# DMXW_Driver_Board.net
KiCad netlist of a schematic drawn in EAGLE
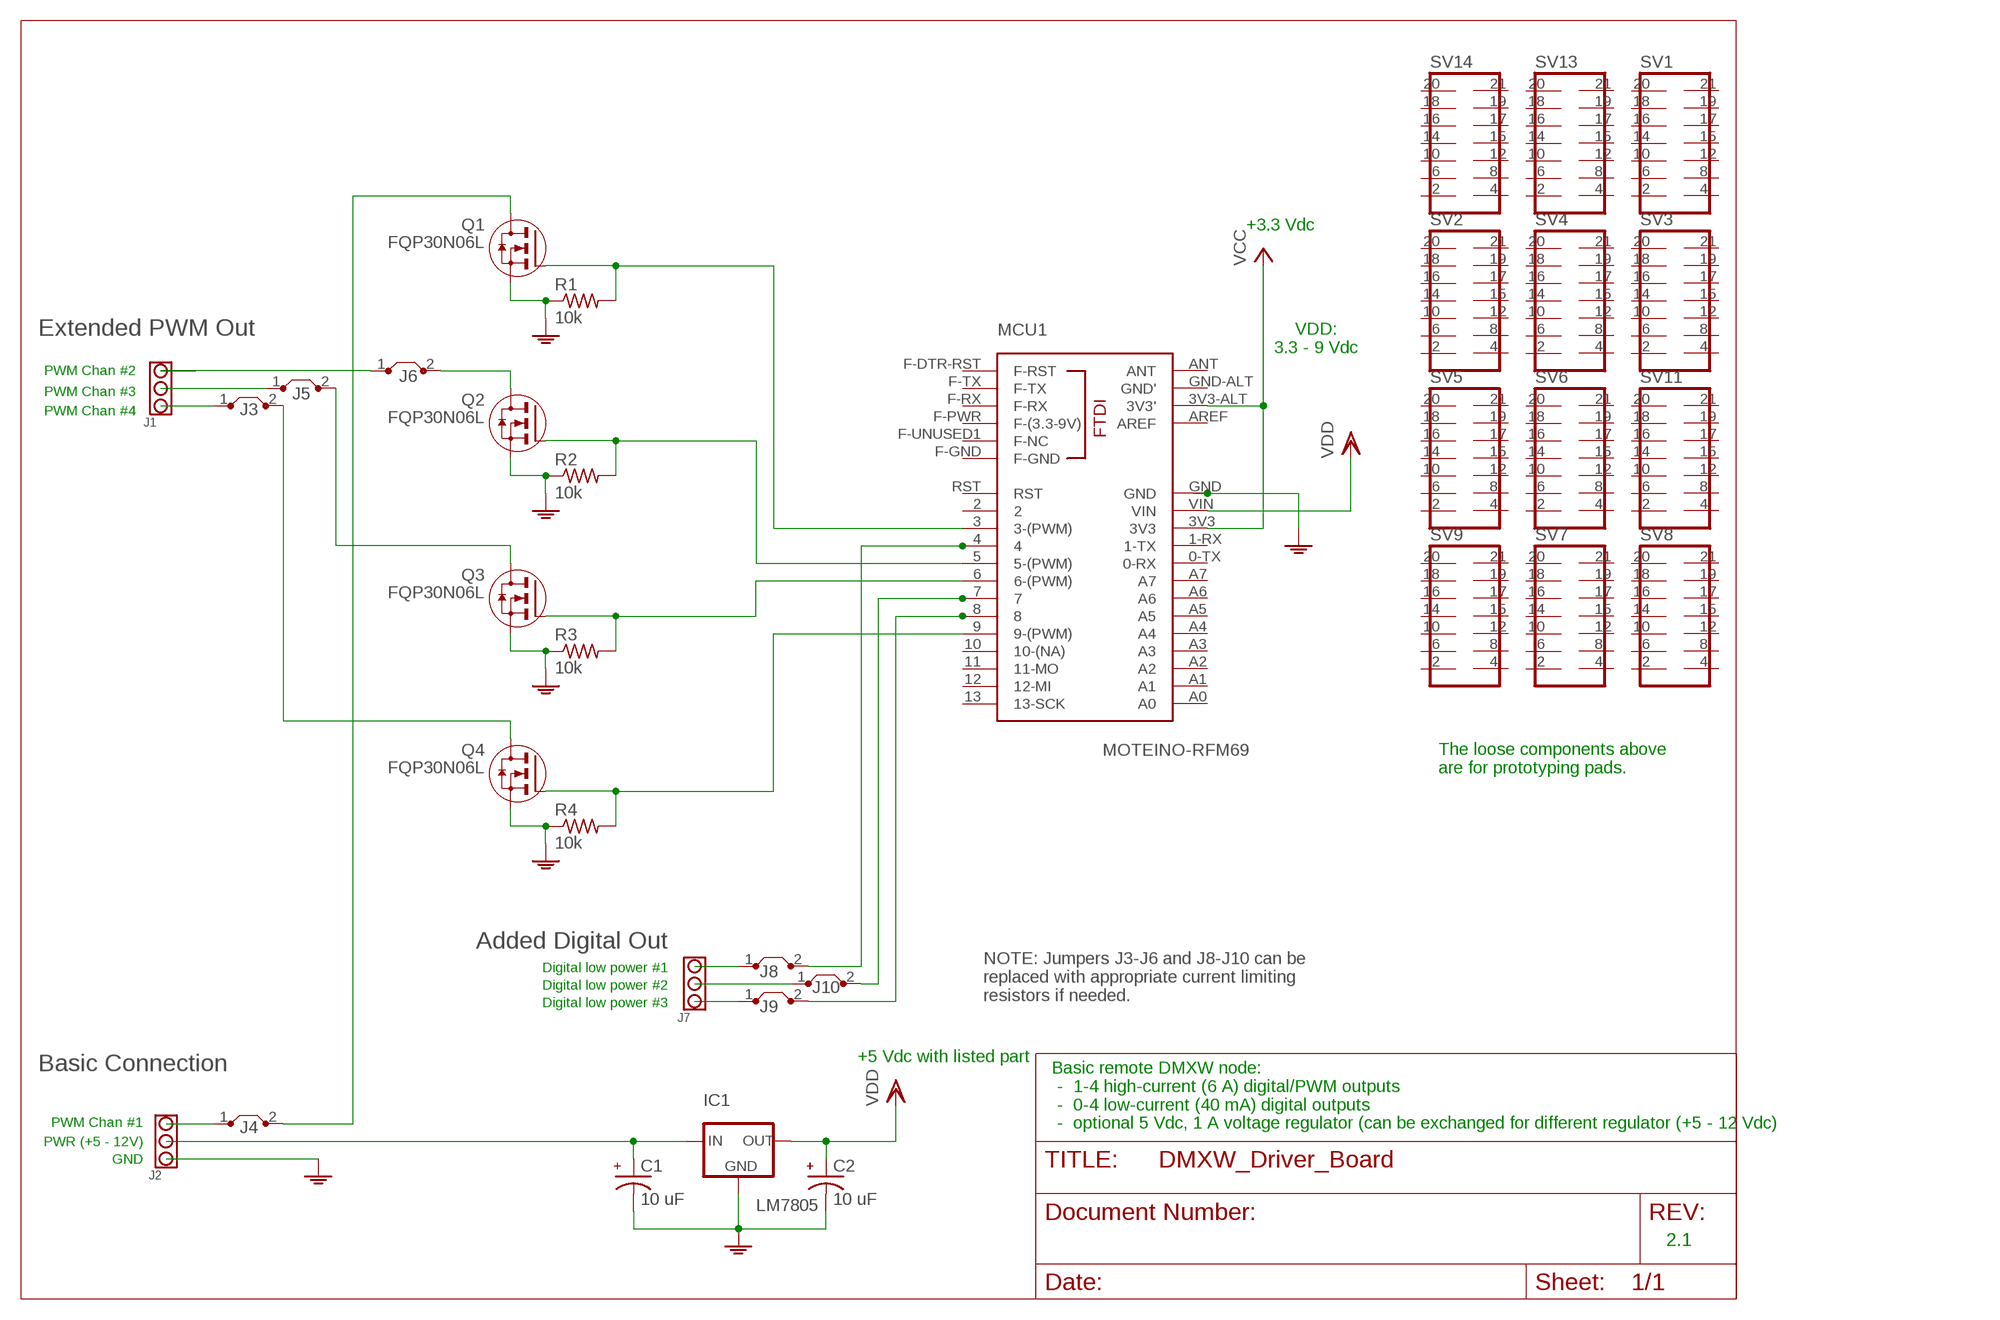
[diagram p0: schematic, sheet 1]

(export (version "E")
  (design (tool "Eeschema 10.0.6"))
  (components
    (comp (ref "C1")
      (value "10 uF")
      (footprint "eagle-import:RADIAL-CANISTER")
      (libsource (lib "eagle-import") (part "CAPACITOR-ELECTROLYTICRADIALCANISTER"))
    )
    (comp (ref "C2")
      (value "10 uF")
      (footprint "eagle-import:RADIAL-CANISTER")
      (libsource (lib "eagle-import") (part "CAPACITOR-ELECTROLYTICRADIALCANISTER"))
    )
    (comp (ref "IC1")
      (value "LM7805")
      (footprint "eagle-import:TO-220-HORIZONTAL")
      (libsource (lib "eagle-import") (part "78XX-VOLTAGEREGULATORSHOZ"))
    )
    (comp (ref "J1")
      (value "TERMINAL-BLOCK-3")
      (footprint "eagle-import:W237-103")
      (libsource (lib "eagle-import") (part "TERMINAL-BLOCK-3"))
    )
    (comp (ref "J2")
      (value "TERMINAL-BLOCK-3")
      (footprint "eagle-import:W237-103")
      (libsource (lib "eagle-import") (part "TERMINAL-BLOCK-3"))
    )
    (comp (ref "J3")
      (value "J5MM")
      (footprint "eagle-import:05")
      (libsource (lib "eagle-import") (part "J5MM"))
    )
    (comp (ref "J4")
      (value "J5MM")
      (footprint "eagle-import:05")
      (libsource (lib "eagle-import") (part "J5MM"))
    )
    (comp (ref "J5")
      (value "J5MM")
      (footprint "eagle-import:05")
      (libsource (lib "eagle-import") (part "J5MM"))
    )
    (comp (ref "J6")
      (value "J5MM")
      (footprint "eagle-import:05")
      (libsource (lib "eagle-import") (part "J5MM"))
    )
    (comp (ref "J7")
      (value "TERMINAL-BLOCK-3")
      (footprint "eagle-import:W237-103")
      (libsource (lib "eagle-import") (part "TERMINAL-BLOCK-3"))
    )
    (comp (ref "J8")
      (value "J5MM")
      (footprint "eagle-import:05")
      (libsource (lib "eagle-import") (part "J5MM"))
    )
    (comp (ref "J9")
      (value "J5MM")
      (footprint "eagle-import:05")
      (libsource (lib "eagle-import") (part "J5MM"))
    )
    (comp (ref "J10")
      (value "J5MM")
      (footprint "eagle-import:05")
      (libsource (lib "eagle-import") (part "J5MM"))
    )
    (comp (ref "MCU1")
      (value "MOTEINO-RFM69")
      (footprint "eagle-import:MOTEINO")
      (libsource (lib "eagle-import") (part "MOTEINO-RFM69"))
    )
    (comp (ref "Q1")
      (value "FQP30N06L")
      (footprint "eagle-import:TO-220-HORIZONTAL")
      (libsource (lib "eagle-import") (part "MOSFET-N-FQP30N06LHORIZ"))
    )
    (comp (ref "Q2")
      (value "FQP30N06L")
      (footprint "eagle-import:TO-220-HORIZONTAL")
      (libsource (lib "eagle-import") (part "MOSFET-N-FQP30N06LHORIZ"))
    )
    (comp (ref "Q3")
      (value "FQP30N06L")
      (footprint "eagle-import:TO-220-HORIZONTAL")
      (libsource (lib "eagle-import") (part "MOSFET-N-FQP30N06LHORIZ"))
    )
    (comp (ref "Q4")
      (value "FQP30N06L")
      (footprint "eagle-import:TO-220-HORIZONTAL")
      (libsource (lib "eagle-import") (part "MOSFET-N-FQP30N06LHORIZ"))
    )
    (comp (ref "R1")
      (value "10k")
      (footprint "eagle-import:0207_10")
      (libsource (lib "eagle-import") (part "R-US_0207/10"))
    )
    (comp (ref "R2")
      (value "10k")
      (footprint "eagle-import:0207_10")
      (libsource (lib "eagle-import") (part "R-US_0207/10"))
    )
    (comp (ref "R3")
      (value "10k")
      (footprint "eagle-import:0207_10")
      (libsource (lib "eagle-import") (part "R-US_0207/10"))
    )
    (comp (ref "R4")
      (value "10k")
      (footprint "eagle-import:0207_10")
      (libsource (lib "eagle-import") (part "R-US_0207/10"))
    )
    (comp (ref "SV1")
      (value "14P")
      (footprint "eagle-import:14P")
      (libsource (lib "eagle-import") (part "14P"))
    )
    (comp (ref "SV2")
      (value "14P")
      (footprint "eagle-import:14P")
      (libsource (lib "eagle-import") (part "14P"))
    )
    (comp (ref "SV3")
      (value "14P")
      (footprint "eagle-import:14P")
      (libsource (lib "eagle-import") (part "14P"))
    )
    (comp (ref "SV4")
      (value "14P")
      (footprint "eagle-import:14P")
      (libsource (lib "eagle-import") (part "14P"))
    )
    (comp (ref "SV5")
      (value "14P")
      (footprint "eagle-import:14P")
      (libsource (lib "eagle-import") (part "14P"))
    )
    (comp (ref "SV6")
      (value "14P")
      (footprint "eagle-import:14P")
      (libsource (lib "eagle-import") (part "14P"))
    )
    (comp (ref "SV7")
      (value "14P")
      (footprint "eagle-import:14P")
      (libsource (lib "eagle-import") (part "14P"))
    )
    (comp (ref "SV8")
      (value "14P")
      (footprint "eagle-import:14P")
      (libsource (lib "eagle-import") (part "14P"))
    )
    (comp (ref "SV9")
      (value "14P")
      (footprint "eagle-import:14P")
      (libsource (lib "eagle-import") (part "14P"))
    )
    (comp (ref "SV11")
      (value "14P")
      (footprint "eagle-import:14P")
      (libsource (lib "eagle-import") (part "14P"))
    )
    (comp (ref "SV13")
      (value "14P")
      (footprint "eagle-import:14P")
      (libsource (lib "eagle-import") (part "14P"))
    )
    (comp (ref "SV14")
      (value "14P")
      (footprint "eagle-import:14P")
      (libsource (lib "eagle-import") (part "14P"))
    )
  )
  (nets
    (net (code "1") (name "GND") (class "Default")
      (node (ref "C1") (pin "-") (pinfunction "-_-") (pintype "passive"))
      (node (ref "C2") (pin "-") (pinfunction "-_-") (pintype "passive"))
      (node (ref "IC1") (pin "PIN2") (pinfunction "GND_PIN2") (pintype "input"))
      (node (ref "J2") (pin "3") (pinfunction "P$3_3") (pintype "bidirectional"))
      (node (ref "MCU1") (pin "GND") (pinfunction "GND_GND") (pintype "bidirectional"))
      (node (ref "Q1") (pin "PIN3") (pinfunction "S_PIN3") (pintype "passive"))
      (node (ref "Q2") (pin "PIN3") (pinfunction "S_PIN3") (pintype "passive"))
      (node (ref "Q3") (pin "PIN3") (pinfunction "S_PIN3") (pintype "passive"))
      (node (ref "Q4") (pin "PIN3") (pinfunction "S_PIN3") (pintype "passive"))
      (node (ref "R1") (pin "1") (pinfunction "1_1") (pintype "passive"))
      (node (ref "R2") (pin "1") (pinfunction "1_1") (pintype "passive"))
      (node (ref "R3") (pin "1") (pinfunction "1_1") (pintype "passive"))
      (node (ref "R4") (pin "1") (pinfunction "1_1") (pintype "passive"))
    )
    (net (code "2") (name "Net-(IC1-IN)") (class "Default")
      (node (ref "C1") (pin "+") (pinfunction "+_+") (pintype "passive"))
      (node (ref "IC1") (pin "PIN1") (pinfunction "IN_PIN1") (pintype "input"))
      (node (ref "J2") (pin "2") (pinfunction "P$2_2") (pintype "bidirectional"))
    )
    (net (code "3") (name "Net-(J1-P$1)") (class "Default")
      (node (ref "J1") (pin "1") (pinfunction "P$1_1") (pintype "bidirectional"))
      (node (ref "J6") (pin "1") (pinfunction "1_1") (pintype "passive"))
    )
    (net (code "4") (name "Net-(J1-P$2)") (class "Default")
      (node (ref "J1") (pin "2") (pinfunction "P$2_2") (pintype "bidirectional"))
      (node (ref "J5") (pin "1") (pinfunction "1_1") (pintype "passive"))
    )
    (net (code "5") (name "Net-(J1-P$3)") (class "Default")
      (node (ref "J1") (pin "3") (pinfunction "P$3_3") (pintype "bidirectional"))
      (node (ref "J3") (pin "1") (pinfunction "1_1") (pintype "passive"))
    )
    (net (code "6") (name "Net-(J2-P$1)") (class "Default")
      (node (ref "J2") (pin "1") (pinfunction "P$1_1") (pintype "bidirectional"))
      (node (ref "J4") (pin "1") (pinfunction "1_1") (pintype "passive"))
    )
    (net (code "7") (name "Net-(J7-P$1)") (class "Default")
      (node (ref "J7") (pin "1") (pinfunction "P$1_1") (pintype "bidirectional"))
      (node (ref "J8") (pin "1") (pinfunction "1_1") (pintype "passive"))
    )
    (net (code "8") (name "Net-(J7-P$2)") (class "Default")
      (node (ref "J10") (pin "1") (pinfunction "1_1") (pintype "passive"))
      (node (ref "J7") (pin "2") (pinfunction "P$2_2") (pintype "bidirectional"))
    )
    (net (code "9") (name "Net-(J7-P$3)") (class "Default")
      (node (ref "J7") (pin "3") (pinfunction "P$3_3") (pintype "bidirectional"))
      (node (ref "J9") (pin "1") (pinfunction "1_1") (pintype "passive"))
    )
    (net (code "10") (name "Net-(J8-Pad2)") (class "Default")
      (node (ref "J8") (pin "2") (pinfunction "2_2") (pintype "passive"))
      (node (ref "MCU1") (pin "4") (pinfunction "4_4") (pintype "bidirectional"))
    )
    (net (code "11") (name "Net-(J9-Pad2)") (class "Default")
      (node (ref "J9") (pin "2") (pinfunction "2_2") (pintype "passive"))
      (node (ref "MCU1") (pin "8") (pinfunction "8_8") (pintype "bidirectional"))
    )
    (net (code "12") (name "Net-(J10-Pad2)") (class "Default")
      (node (ref "J10") (pin "2") (pinfunction "2_2") (pintype "passive"))
      (node (ref "MCU1") (pin "7") (pinfunction "7_7") (pintype "bidirectional"))
    )
    (net (code "13") (name "Net-(MCU1-3-(PWM))") (class "Default")
      (node (ref "MCU1") (pin "3") (pinfunction "3-(PWM)_3") (pintype "bidirectional"))
      (node (ref "Q1") (pin "PIN1") (pinfunction "G_PIN1") (pintype "passive"))
      (node (ref "R1") (pin "2") (pinfunction "2_2") (pintype "passive"))
    )
    (net (code "14") (name "Net-(MCU1-5-(PWM))") (class "Default")
      (node (ref "MCU1") (pin "5") (pinfunction "5-(PWM)_5") (pintype "bidirectional"))
      (node (ref "Q2") (pin "PIN1") (pinfunction "G_PIN1") (pintype "passive"))
      (node (ref "R2") (pin "2") (pinfunction "2_2") (pintype "passive"))
    )
    (net (code "15") (name "Net-(MCU1-6-(PWM))") (class "Default")
      (node (ref "MCU1") (pin "6") (pinfunction "6-(PWM)_6") (pintype "bidirectional"))
      (node (ref "Q3") (pin "PIN1") (pinfunction "G_PIN1") (pintype "passive"))
      (node (ref "R3") (pin "2") (pinfunction "2_2") (pintype "passive"))
    )
    (net (code "16") (name "Net-(MCU1-9-(PWM))") (class "Default")
      (node (ref "MCU1") (pin "9") (pinfunction "9-(PWM)_9") (pintype "bidirectional"))
      (node (ref "Q4") (pin "PIN1") (pinfunction "G_PIN1") (pintype "passive"))
      (node (ref "R4") (pin "2") (pinfunction "2_2") (pintype "passive"))
    )
    (net (code "17") (name "Net-(Q1-D)") (class "Default")
      (node (ref "J4") (pin "2") (pinfunction "2_2") (pintype "passive"))
      (node (ref "Q1") (pin "PIN2") (pinfunction "D_PIN2") (pintype "passive"))
    )
    (net (code "18") (name "Net-(Q2-D)") (class "Default")
      (node (ref "J6") (pin "2") (pinfunction "2_2") (pintype "passive"))
      (node (ref "Q2") (pin "PIN2") (pinfunction "D_PIN2") (pintype "passive"))
    )
    (net (code "19") (name "Net-(Q3-D)") (class "Default")
      (node (ref "J5") (pin "2") (pinfunction "2_2") (pintype "passive"))
      (node (ref "Q3") (pin "PIN2") (pinfunction "D_PIN2") (pintype "passive"))
    )
    (net (code "20") (name "Net-(Q4-D)") (class "Default")
      (node (ref "J3") (pin "2") (pinfunction "2_2") (pintype "passive"))
      (node (ref "Q4") (pin "PIN2") (pinfunction "D_PIN2") (pintype "passive"))
    )
    (net (code "21") (name "VCC") (class "Default")
      (node (ref "MCU1") (pin "3V3") (pinfunction "3V3_3V3") (pintype "bidirectional"))
      (node (ref "MCU1") (pin "3V3-ALT") (pinfunction "3V3'_3V3-ALT") (pintype "bidirectional"))
    )
    (net (code "22") (name "VDD") (class "Default")
      (node (ref "C2") (pin "+") (pinfunction "+_+") (pintype "passive"))
      (node (ref "IC1") (pin "PIN3") (pinfunction "OUT_PIN3") (pintype "passive"))
      (node (ref "MCU1") (pin "VIN") (pinfunction "VIN_VIN") (pintype "bidirectional"))
    )
    (net (code "23") (name "unconnected-(MCU1-0-RX-Pad0-TX)") (class "Default")
      (node (ref "MCU1") (pin "0-TX") (pinfunction "0-RX_0-TX") (pintype "bidirectional"))
    )
    (net (code "24") (name "unconnected-(MCU1-1-TX-Pad1-RX)") (class "Default")
      (node (ref "MCU1") (pin "1-RX") (pinfunction "1-TX_1-RX") (pintype "bidirectional"))
    )
    (net (code "25") (name "unconnected-(MCU1-10-(NA)-Pad10)") (class "Default")
      (node (ref "MCU1") (pin "10") (pinfunction "10-(NA)_10") (pintype "bidirectional"))
    )
    (net (code "26") (name "unconnected-(MCU1-11-MO-Pad11)") (class "Default")
      (node (ref "MCU1") (pin "11") (pinfunction "11-MO_11") (pintype "bidirectional"))
    )
    (net (code "27") (name "unconnected-(MCU1-12-MI-Pad12)") (class "Default")
      (node (ref "MCU1") (pin "12") (pinfunction "12-MI_12") (pintype "bidirectional"))
    )
    (net (code "28") (name "unconnected-(MCU1-13-SCK-Pad13)") (class "Default")
      (node (ref "MCU1") (pin "13") (pinfunction "13-SCK_13") (pintype "bidirectional"))
    )
    (net (code "29") (name "unconnected-(MCU1-F-(3.3-9V)-PadF-PWR)") (class "Default")
      (node (ref "MCU1") (pin "F-PWR") (pinfunction "F-(3.3-9V)_F-PWR") (pintype "bidirectional"))
    )
    (net (code "30") (name "unconnected-(MCU1-F-NC-PadF-UNUSED1)") (class "Default")
      (node (ref "MCU1") (pin "F-UNUSED1") (pinfunction "F-NC_F-UNUSED1") (pintype "bidirectional"))
    )
    (net (code "31") (name "unconnected-(MCU1-F-RST-PadF-DTR-RST)") (class "Default")
      (node (ref "MCU1") (pin "F-DTR-RST") (pinfunction "F-RST_F-DTR-RST") (pintype "bidirectional"))
    )
    (net (code "32") (name "unconnected-(MCU1-GND'-PadGND-ALT)") (class "Default")
      (node (ref "MCU1") (pin "GND-ALT") (pinfunction "GND'_GND-ALT") (pintype "bidirectional"))
    )
    (net (code "33") (name "unconnected-(MCU1-Pad2)") (class "Default")
      (node (ref "MCU1") (pin "2") (pinfunction "2_2") (pintype "bidirectional"))
    )
    (net (code "34") (name "unconnected-(MCU1-PadA0)") (class "Default")
      (node (ref "MCU1") (pin "A0") (pinfunction "A0_A0") (pintype "bidirectional"))
    )
    (net (code "35") (name "unconnected-(MCU1-PadA1)") (class "Default")
      (node (ref "MCU1") (pin "A1") (pinfunction "A1_A1") (pintype "bidirectional"))
    )
    (net (code "36") (name "unconnected-(MCU1-PadA2)") (class "Default")
      (node (ref "MCU1") (pin "A2") (pinfunction "A2_A2") (pintype "bidirectional"))
    )
    (net (code "37") (name "unconnected-(MCU1-PadA3)") (class "Default")
      (node (ref "MCU1") (pin "A3") (pinfunction "A3_A3") (pintype "bidirectional"))
    )
    (net (code "38") (name "unconnected-(MCU1-PadA4)") (class "Default")
      (node (ref "MCU1") (pin "A4") (pinfunction "A4_A4") (pintype "bidirectional"))
    )
    (net (code "39") (name "unconnected-(MCU1-PadA5)") (class "Default")
      (node (ref "MCU1") (pin "A5") (pinfunction "A5_A5") (pintype "bidirectional"))
    )
    (net (code "40") (name "unconnected-(MCU1-PadA6)") (class "Default")
      (node (ref "MCU1") (pin "A6") (pinfunction "A6_A6") (pintype "bidirectional"))
    )
    (net (code "41") (name "unconnected-(MCU1-PadA7)") (class "Default")
      (node (ref "MCU1") (pin "A7") (pinfunction "A7_A7") (pintype "bidirectional"))
    )
    (net (code "42") (name "unconnected-(MCU1-PadANT)") (class "Default")
      (node (ref "MCU1") (pin "ANT") (pinfunction "ANT_ANT") (pintype "bidirectional"))
    )
    (net (code "43") (name "unconnected-(MCU1-PadAREF)") (class "Default")
      (node (ref "MCU1") (pin "AREF") (pinfunction "AREF_AREF") (pintype "bidirectional"))
    )
    (net (code "44") (name "unconnected-(MCU1-PadF-GND)") (class "Default")
      (node (ref "MCU1") (pin "F-GND") (pinfunction "F-GND_F-GND") (pintype "bidirectional"))
    )
    (net (code "45") (name "unconnected-(MCU1-PadF-RX)") (class "Default")
      (node (ref "MCU1") (pin "F-RX") (pinfunction "F-RX_F-RX") (pintype "bidirectional"))
    )
    (net (code "46") (name "unconnected-(MCU1-PadF-TX)") (class "Default")
      (node (ref "MCU1") (pin "F-TX") (pinfunction "F-TX_F-TX") (pintype "bidirectional"))
    )
    (net (code "47") (name "unconnected-(MCU1-PadRST)") (class "Default")
      (node (ref "MCU1") (pin "RST") (pinfunction "RST_RST") (pintype "bidirectional"))
    )
    (net (code "48") (name "unconnected-(SV1-1-Pad2)") (class "Default")
      (node (ref "SV1") (pin "2") (pinfunction "1_2") (pintype "passive"))
    )
    (net (code "49") (name "unconnected-(SV1-2-Pad4)") (class "Default")
      (node (ref "SV1") (pin "4") (pinfunction "2_4") (pintype "passive"))
    )
    (net (code "50") (name "unconnected-(SV1-3-Pad6)") (class "Default")
      (node (ref "SV1") (pin "6") (pinfunction "3_6") (pintype "passive"))
    )
    (net (code "51") (name "unconnected-(SV1-4-Pad8)") (class "Default")
      (node (ref "SV1") (pin "8") (pinfunction "4_8") (pintype "passive"))
    )
    (net (code "52") (name "unconnected-(SV1-5-Pad10)") (class "Default")
      (node (ref "SV1") (pin "10") (pinfunction "5_10") (pintype "passive"))
    )
    (net (code "53") (name "unconnected-(SV1-6-Pad12)") (class "Default")
      (node (ref "SV1") (pin "12") (pinfunction "6_12") (pintype "passive"))
    )
    (net (code "54") (name "unconnected-(SV1-7-Pad14)") (class "Default")
      (node (ref "SV1") (pin "14") (pinfunction "7_14") (pintype "passive"))
    )
    (net (code "55") (name "unconnected-(SV1-8-Pad15)") (class "Default")
      (node (ref "SV1") (pin "15") (pinfunction "8_15") (pintype "passive"))
    )
    (net (code "56") (name "unconnected-(SV1-9-Pad16)") (class "Default")
      (node (ref "SV1") (pin "16") (pinfunction "9_16") (pintype "passive"))
    )
    (net (code "57") (name "unconnected-(SV1-10-Pad17)") (class "Default")
      (node (ref "SV1") (pin "17") (pinfunction "10_17") (pintype "passive"))
    )
    (net (code "58") (name "unconnected-(SV1-11-Pad18)") (class "Default")
      (node (ref "SV1") (pin "18") (pinfunction "11_18") (pintype "passive"))
    )
    (net (code "59") (name "unconnected-(SV1-12-Pad19)") (class "Default")
      (node (ref "SV1") (pin "19") (pinfunction "12_19") (pintype "passive"))
    )
    (net (code "60") (name "unconnected-(SV1-13-Pad20)") (class "Default")
      (node (ref "SV1") (pin "20") (pinfunction "13_20") (pintype "passive"))
    )
    (net (code "61") (name "unconnected-(SV1-14-Pad21)") (class "Default")
      (node (ref "SV1") (pin "21") (pinfunction "14_21") (pintype "passive"))
    )
    (net (code "62") (name "unconnected-(SV2-1-Pad2)") (class "Default")
      (node (ref "SV2") (pin "2") (pinfunction "1_2") (pintype "passive"))
    )
    (net (code "63") (name "unconnected-(SV2-2-Pad4)") (class "Default")
      (node (ref "SV2") (pin "4") (pinfunction "2_4") (pintype "passive"))
    )
    (net (code "64") (name "unconnected-(SV2-3-Pad6)") (class "Default")
      (node (ref "SV2") (pin "6") (pinfunction "3_6") (pintype "passive"))
    )
    (net (code "65") (name "unconnected-(SV2-4-Pad8)") (class "Default")
      (node (ref "SV2") (pin "8") (pinfunction "4_8") (pintype "passive"))
    )
    (net (code "66") (name "unconnected-(SV2-5-Pad10)") (class "Default")
      (node (ref "SV2") (pin "10") (pinfunction "5_10") (pintype "passive"))
    )
    (net (code "67") (name "unconnected-(SV2-6-Pad12)") (class "Default")
      (node (ref "SV2") (pin "12") (pinfunction "6_12") (pintype "passive"))
    )
    (net (code "68") (name "unconnected-(SV2-7-Pad14)") (class "Default")
      (node (ref "SV2") (pin "14") (pinfunction "7_14") (pintype "passive"))
    )
    (net (code "69") (name "unconnected-(SV2-8-Pad15)") (class "Default")
      (node (ref "SV2") (pin "15") (pinfunction "8_15") (pintype "passive"))
    )
    (net (code "70") (name "unconnected-(SV2-9-Pad16)") (class "Default")
      (node (ref "SV2") (pin "16") (pinfunction "9_16") (pintype "passive"))
    )
    (net (code "71") (name "unconnected-(SV2-10-Pad17)") (class "Default")
      (node (ref "SV2") (pin "17") (pinfunction "10_17") (pintype "passive"))
    )
    (net (code "72") (name "unconnected-(SV2-11-Pad18)") (class "Default")
      (node (ref "SV2") (pin "18") (pinfunction "11_18") (pintype "passive"))
    )
    (net (code "73") (name "unconnected-(SV2-12-Pad19)") (class "Default")
      (node (ref "SV2") (pin "19") (pinfunction "12_19") (pintype "passive"))
    )
    (net (code "74") (name "unconnected-(SV2-13-Pad20)") (class "Default")
      (node (ref "SV2") (pin "20") (pinfunction "13_20") (pintype "passive"))
    )
    (net (code "75") (name "unconnected-(SV2-14-Pad21)") (class "Default")
      (node (ref "SV2") (pin "21") (pinfunction "14_21") (pintype "passive"))
    )
    (net (code "76") (name "unconnected-(SV3-1-Pad2)") (class "Default")
      (node (ref "SV3") (pin "2") (pinfunction "1_2") (pintype "passive"))
    )
    (net (code "77") (name "unconnected-(SV3-2-Pad4)") (class "Default")
      (node (ref "SV3") (pin "4") (pinfunction "2_4") (pintype "passive"))
    )
    (net (code "78") (name "unconnected-(SV3-3-Pad6)") (class "Default")
      (node (ref "SV3") (pin "6") (pinfunction "3_6") (pintype "passive"))
    )
    (net (code "79") (name "unconnected-(SV3-4-Pad8)") (class "Default")
      (node (ref "SV3") (pin "8") (pinfunction "4_8") (pintype "passive"))
    )
    (net (code "80") (name "unconnected-(SV3-5-Pad10)") (class "Default")
      (node (ref "SV3") (pin "10") (pinfunction "5_10") (pintype "passive"))
    )
    (net (code "81") (name "unconnected-(SV3-6-Pad12)") (class "Default")
      (node (ref "SV3") (pin "12") (pinfunction "6_12") (pintype "passive"))
    )
    (net (code "82") (name "unconnected-(SV3-7-Pad14)") (class "Default")
      (node (ref "SV3") (pin "14") (pinfunction "7_14") (pintype "passive"))
    )
    (net (code "83") (name "unconnected-(SV3-8-Pad15)") (class "Default")
      (node (ref "SV3") (pin "15") (pinfunction "8_15") (pintype "passive"))
    )
    (net (code "84") (name "unconnected-(SV3-9-Pad16)") (class "Default")
      (node (ref "SV3") (pin "16") (pinfunction "9_16") (pintype "passive"))
    )
    (net (code "85") (name "unconnected-(SV3-10-Pad17)") (class "Default")
      (node (ref "SV3") (pin "17") (pinfunction "10_17") (pintype "passive"))
    )
    (net (code "86") (name "unconnected-(SV3-11-Pad18)") (class "Default")
      (node (ref "SV3") (pin "18") (pinfunction "11_18") (pintype "passive"))
    )
    (net (code "87") (name "unconnected-(SV3-12-Pad19)") (class "Default")
      (node (ref "SV3") (pin "19") (pinfunction "12_19") (pintype "passive"))
    )
    (net (code "88") (name "unconnected-(SV3-13-Pad20)") (class "Default")
      (node (ref "SV3") (pin "20") (pinfunction "13_20") (pintype "passive"))
    )
    (net (code "89") (name "unconnected-(SV3-14-Pad21)") (class "Default")
      (node (ref "SV3") (pin "21") (pinfunction "14_21") (pintype "passive"))
    )
    (net (code "90") (name "unconnected-(SV4-1-Pad2)") (class "Default")
      (node (ref "SV4") (pin "2") (pinfunction "1_2") (pintype "passive"))
    )
    (net (code "91") (name "unconnected-(SV4-2-Pad4)") (class "Default")
      (node (ref "SV4") (pin "4") (pinfunction "2_4") (pintype "passive"))
    )
    (net (code "92") (name "unconnected-(SV4-3-Pad6)") (class "Default")
      (node (ref "SV4") (pin "6") (pinfunction "3_6") (pintype "passive"))
    )
    (net (code "93") (name "unconnected-(SV4-4-Pad8)") (class "Default")
      (node (ref "SV4") (pin "8") (pinfunction "4_8") (pintype "passive"))
    )
    (net (code "94") (name "unconnected-(SV4-5-Pad10)") (class "Default")
      (node (ref "SV4") (pin "10") (pinfunction "5_10") (pintype "passive"))
    )
    (net (code "95") (name "unconnected-(SV4-6-Pad12)") (class "Default")
      (node (ref "SV4") (pin "12") (pinfunction "6_12") (pintype "passive"))
    )
    (net (code "96") (name "unconnected-(SV4-7-Pad14)") (class "Default")
      (node (ref "SV4") (pin "14") (pinfunction "7_14") (pintype "passive"))
    )
    (net (code "97") (name "unconnected-(SV4-8-Pad15)") (class "Default")
      (node (ref "SV4") (pin "15") (pinfunction "8_15") (pintype "passive"))
    )
    (net (code "98") (name "unconnected-(SV4-9-Pad16)") (class "Default")
      (node (ref "SV4") (pin "16") (pinfunction "9_16") (pintype "passive"))
    )
    (net (code "99") (name "unconnected-(SV4-10-Pad17)") (class "Default")
      (node (ref "SV4") (pin "17") (pinfunction "10_17") (pintype "passive"))
    )
    (net (code "100") (name "unconnected-(SV4-11-Pad18)") (class "Default")
      (node (ref "SV4") (pin "18") (pinfunction "11_18") (pintype "passive"))
    )
    (net (code "101") (name "unconnected-(SV4-12-Pad19)") (class "Default")
      (node (ref "SV4") (pin "19") (pinfunction "12_19") (pintype "passive"))
    )
    (net (code "102") (name "unconnected-(SV4-13-Pad20)") (class "Default")
      (node (ref "SV4") (pin "20") (pinfunction "13_20") (pintype "passive"))
    )
    (net (code "103") (name "unconnected-(SV4-14-Pad21)") (class "Default")
      (node (ref "SV4") (pin "21") (pinfunction "14_21") (pintype "passive"))
    )
    (net (code "104") (name "unconnected-(SV5-1-Pad2)") (class "Default")
      (node (ref "SV5") (pin "2") (pinfunction "1_2") (pintype "passive"))
    )
    (net (code "105") (name "unconnected-(SV5-2-Pad4)") (class "Default")
      (node (ref "SV5") (pin "4") (pinfunction "2_4") (pintype "passive"))
    )
    (net (code "106") (name "unconnected-(SV5-3-Pad6)") (class "Default")
      (node (ref "SV5") (pin "6") (pinfunction "3_6") (pintype "passive"))
    )
    (net (code "107") (name "unconnected-(SV5-4-Pad8)") (class "Default")
      (node (ref "SV5") (pin "8") (pinfunction "4_8") (pintype "passive"))
    )
    (net (code "108") (name "unconnected-(SV5-5-Pad10)") (class "Default")
      (node (ref "SV5") (pin "10") (pinfunction "5_10") (pintype "passive"))
    )
    (net (code "109") (name "unconnected-(SV5-6-Pad12)") (class "Default")
      (node (ref "SV5") (pin "12") (pinfunction "6_12") (pintype "passive"))
    )
    (net (code "110") (name "unconnected-(SV5-7-Pad14)") (class "Default")
      (node (ref "SV5") (pin "14") (pinfunction "7_14") (pintype "passive"))
    )
    (net (code "111") (name "unconnected-(SV5-8-Pad15)") (class "Default")
      (node (ref "SV5") (pin "15") (pinfunction "8_15") (pintype "passive"))
    )
    (net (code "112") (name "unconnected-(SV5-9-Pad16)") (class "Default")
      (node (ref "SV5") (pin "16") (pinfunction "9_16") (pintype "passive"))
    )
    (net (code "113") (name "unconnected-(SV5-10-Pad17)") (class "Default")
      (node (ref "SV5") (pin "17") (pinfunction "10_17") (pintype "passive"))
    )
    (net (code "114") (name "unconnected-(SV5-11-Pad18)") (class "Default")
      (node (ref "SV5") (pin "18") (pinfunction "11_18") (pintype "passive"))
    )
    (net (code "115") (name "unconnected-(SV5-12-Pad19)") (class "Default")
      (node (ref "SV5") (pin "19") (pinfunction "12_19") (pintype "passive"))
    )
    (net (code "116") (name "unconnected-(SV5-13-Pad20)") (class "Default")
      (node (ref "SV5") (pin "20") (pinfunction "13_20") (pintype "passive"))
    )
    (net (code "117") (name "unconnected-(SV5-14-Pad21)") (class "Default")
      (node (ref "SV5") (pin "21") (pinfunction "14_21") (pintype "passive"))
    )
    (net (code "118") (name "unconnected-(SV6-1-Pad2)") (class "Default")
      (node (ref "SV6") (pin "2") (pinfunction "1_2") (pintype "passive"))
    )
    (net (code "119") (name "unconnected-(SV6-2-Pad4)") (class "Default")
      (node (ref "SV6") (pin "4") (pinfunction "2_4") (pintype "passive"))
    )
    (net (code "120") (name "unconnected-(SV6-3-Pad6)") (class "Default")
      (node (ref "SV6") (pin "6") (pinfunction "3_6") (pintype "passive"))
    )
    (net (code "121") (name "unconnected-(SV6-4-Pad8)") (class "Default")
      (node (ref "SV6") (pin "8") (pinfunction "4_8") (pintype "passive"))
    )
    (net (code "122") (name "unconnected-(SV6-5-Pad10)") (class "Default")
      (node (ref "SV6") (pin "10") (pinfunction "5_10") (pintype "passive"))
    )
    (net (code "123") (name "unconnected-(SV6-6-Pad12)") (class "Default")
      (node (ref "SV6") (pin "12") (pinfunction "6_12") (pintype "passive"))
    )
    (net (code "124") (name "unconnected-(SV6-7-Pad14)") (class "Default")
      (node (ref "SV6") (pin "14") (pinfunction "7_14") (pintype "passive"))
    )
    (net (code "125") (name "unconnected-(SV6-8-Pad15)") (class "Default")
      (node (ref "SV6") (pin "15") (pinfunction "8_15") (pintype "passive"))
    )
    (net (code "126") (name "unconnected-(SV6-9-Pad16)") (class "Default")
      (node (ref "SV6") (pin "16") (pinfunction "9_16") (pintype "passive"))
    )
    (net (code "127") (name "unconnected-(SV6-10-Pad17)") (class "Default")
      (node (ref "SV6") (pin "17") (pinfunction "10_17") (pintype "passive"))
    )
    (net (code "128") (name "unconnected-(SV6-11-Pad18)") (class "Default")
      (node (ref "SV6") (pin "18") (pinfunction "11_18") (pintype "passive"))
    )
    (net (code "129") (name "unconnected-(SV6-12-Pad19)") (class "Default")
      (node (ref "SV6") (pin "19") (pinfunction "12_19") (pintype "passive"))
    )
    (net (code "130") (name "unconnected-(SV6-13-Pad20)") (class "Default")
      (node (ref "SV6") (pin "20") (pinfunction "13_20") (pintype "passive"))
    )
    (net (code "131") (name "unconnected-(SV6-14-Pad21)") (class "Default")
      (node (ref "SV6") (pin "21") (pinfunction "14_21") (pintype "passive"))
    )
    (net (code "132") (name "unconnected-(SV7-1-Pad2)") (class "Default")
      (node (ref "SV7") (pin "2") (pinfunction "1_2") (pintype "passive"))
    )
    (net (code "133") (name "unconnected-(SV7-2-Pad4)") (class "Default")
      (node (ref "SV7") (pin "4") (pinfunction "2_4") (pintype "passive"))
    )
    (net (code "134") (name "unconnected-(SV7-3-Pad6)") (class "Default")
      (node (ref "SV7") (pin "6") (pinfunction "3_6") (pintype "passive"))
    )
    (net (code "135") (name "unconnected-(SV7-4-Pad8)") (class "Default")
      (node (ref "SV7") (pin "8") (pinfunction "4_8") (pintype "passive"))
    )
    (net (code "136") (name "unconnected-(SV7-5-Pad10)") (class "Default")
      (node (ref "SV7") (pin "10") (pinfunction "5_10") (pintype "passive"))
    )
    (net (code "137") (name "unconnected-(SV7-6-Pad12)") (class "Default")
      (node (ref "SV7") (pin "12") (pinfunction "6_12") (pintype "passive"))
    )
    (net (code "138") (name "unconnected-(SV7-7-Pad14)") (class "Default")
      (node (ref "SV7") (pin "14") (pinfunction "7_14") (pintype "passive"))
    )
    (net (code "139") (name "unconnected-(SV7-8-Pad15)") (class "Default")
      (node (ref "SV7") (pin "15") (pinfunction "8_15") (pintype "passive"))
    )
    (net (code "140") (name "unconnected-(SV7-9-Pad16)") (class "Default")
      (node (ref "SV7") (pin "16") (pinfunction "9_16") (pintype "passive"))
    )
    (net (code "141") (name "unconnected-(SV7-10-Pad17)") (class "Default")
      (node (ref "SV7") (pin "17") (pinfunction "10_17") (pintype "passive"))
    )
    (net (code "142") (name "unconnected-(SV7-11-Pad18)") (class "Default")
      (node (ref "SV7") (pin "18") (pinfunction "11_18") (pintype "passive"))
    )
    (net (code "143") (name "unconnected-(SV7-12-Pad19)") (class "Default")
      (node (ref "SV7") (pin "19") (pinfunction "12_19") (pintype "passive"))
    )
    (net (code "144") (name "unconnected-(SV7-13-Pad20)") (class "Default")
      (node (ref "SV7") (pin "20") (pinfunction "13_20") (pintype "passive"))
    )
    (net (code "145") (name "unconnected-(SV7-14-Pad21)") (class "Default")
      (node (ref "SV7") (pin "21") (pinfunction "14_21") (pintype "passive"))
    )
    (net (code "146") (name "unconnected-(SV8-1-Pad2)") (class "Default")
      (node (ref "SV8") (pin "2") (pinfunction "1_2") (pintype "passive"))
    )
    (net (code "147") (name "unconnected-(SV8-2-Pad4)") (class "Default")
      (node (ref "SV8") (pin "4") (pinfunction "2_4") (pintype "passive"))
    )
    (net (code "148") (name "unconnected-(SV8-3-Pad6)") (class "Default")
      (node (ref "SV8") (pin "6") (pinfunction "3_6") (pintype "passive"))
    )
    (net (code "149") (name "unconnected-(SV8-4-Pad8)") (class "Default")
      (node (ref "SV8") (pin "8") (pinfunction "4_8") (pintype "passive"))
    )
    (net (code "150") (name "unconnected-(SV8-5-Pad10)") (class "Default")
      (node (ref "SV8") (pin "10") (pinfunction "5_10") (pintype "passive"))
    )
    (net (code "151") (name "unconnected-(SV8-6-Pad12)") (class "Default")
      (node (ref "SV8") (pin "12") (pinfunction "6_12") (pintype "passive"))
    )
    (net (code "152") (name "unconnected-(SV8-7-Pad14)") (class "Default")
      (node (ref "SV8") (pin "14") (pinfunction "7_14") (pintype "passive"))
    )
    (net (code "153") (name "unconnected-(SV8-8-Pad15)") (class "Default")
      (node (ref "SV8") (pin "15") (pinfunction "8_15") (pintype "passive"))
    )
    (net (code "154") (name "unconnected-(SV8-9-Pad16)") (class "Default")
      (node (ref "SV8") (pin "16") (pinfunction "9_16") (pintype "passive"))
    )
    (net (code "155") (name "unconnected-(SV8-10-Pad17)") (class "Default")
      (node (ref "SV8") (pin "17") (pinfunction "10_17") (pintype "passive"))
    )
    (net (code "156") (name "unconnected-(SV8-11-Pad18)") (class "Default")
      (node (ref "SV8") (pin "18") (pinfunction "11_18") (pintype "passive"))
    )
    (net (code "157") (name "unconnected-(SV8-12-Pad19)") (class "Default")
      (node (ref "SV8") (pin "19") (pinfunction "12_19") (pintype "passive"))
    )
    (net (code "158") (name "unconnected-(SV8-13-Pad20)") (class "Default")
      (node (ref "SV8") (pin "20") (pinfunction "13_20") (pintype "passive"))
    )
    (net (code "159") (name "unconnected-(SV8-14-Pad21)") (class "Default")
      (node (ref "SV8") (pin "21") (pinfunction "14_21") (pintype "passive"))
    )
    (net (code "160") (name "unconnected-(SV9-1-Pad2)") (class "Default")
      (node (ref "SV9") (pin "2") (pinfunction "1_2") (pintype "passive"))
    )
    (net (code "161") (name "unconnected-(SV9-2-Pad4)") (class "Default")
      (node (ref "SV9") (pin "4") (pinfunction "2_4") (pintype "passive"))
    )
    (net (code "162") (name "unconnected-(SV9-3-Pad6)") (class "Default")
      (node (ref "SV9") (pin "6") (pinfunction "3_6") (pintype "passive"))
    )
    (net (code "163") (name "unconnected-(SV9-4-Pad8)") (class "Default")
      (node (ref "SV9") (pin "8") (pinfunction "4_8") (pintype "passive"))
    )
    (net (code "164") (name "unconnected-(SV9-5-Pad10)") (class "Default")
      (node (ref "SV9") (pin "10") (pinfunction "5_10") (pintype "passive"))
    )
    (net (code "165") (name "unconnected-(SV9-6-Pad12)") (class "Default")
      (node (ref "SV9") (pin "12") (pinfunction "6_12") (pintype "passive"))
    )
    (net (code "166") (name "unconnected-(SV9-7-Pad14)") (class "Default")
      (node (ref "SV9") (pin "14") (pinfunction "7_14") (pintype "passive"))
    )
    (net (code "167") (name "unconnected-(SV9-8-Pad15)") (class "Default")
      (node (ref "SV9") (pin "15") (pinfunction "8_15") (pintype "passive"))
    )
    (net (code "168") (name "unconnected-(SV9-9-Pad16)") (class "Default")
      (node (ref "SV9") (pin "16") (pinfunction "9_16") (pintype "passive"))
    )
    (net (code "169") (name "unconnected-(SV9-10-Pad17)") (class "Default")
      (node (ref "SV9") (pin "17") (pinfunction "10_17") (pintype "passive"))
    )
    (net (code "170") (name "unconnected-(SV9-11-Pad18)") (class "Default")
      (node (ref "SV9") (pin "18") (pinfunction "11_18") (pintype "passive"))
    )
    (net (code "171") (name "unconnected-(SV9-12-Pad19)") (class "Default")
      (node (ref "SV9") (pin "19") (pinfunction "12_19") (pintype "passive"))
    )
    (net (code "172") (name "unconnected-(SV9-13-Pad20)") (class "Default")
      (node (ref "SV9") (pin "20") (pinfunction "13_20") (pintype "passive"))
    )
    (net (code "173") (name "unconnected-(SV9-14-Pad21)") (class "Default")
      (node (ref "SV9") (pin "21") (pinfunction "14_21") (pintype "passive"))
    )
    (net (code "174") (name "unconnected-(SV11-1-Pad2)") (class "Default")
      (node (ref "SV11") (pin "2") (pinfunction "1_2") (pintype "passive"))
    )
    (net (code "175") (name "unconnected-(SV11-2-Pad4)") (class "Default")
      (node (ref "SV11") (pin "4") (pinfunction "2_4") (pintype "passive"))
    )
    (net (code "176") (name "unconnected-(SV11-3-Pad6)") (class "Default")
      (node (ref "SV11") (pin "6") (pinfunction "3_6") (pintype "passive"))
    )
    (net (code "177") (name "unconnected-(SV11-4-Pad8)") (class "Default")
      (node (ref "SV11") (pin "8") (pinfunction "4_8") (pintype "passive"))
    )
    (net (code "178") (name "unconnected-(SV11-5-Pad10)") (class "Default")
      (node (ref "SV11") (pin "10") (pinfunction "5_10") (pintype "passive"))
    )
    (net (code "179") (name "unconnected-(SV11-6-Pad12)") (class "Default")
      (node (ref "SV11") (pin "12") (pinfunction "6_12") (pintype "passive"))
    )
    (net (code "180") (name "unconnected-(SV11-7-Pad14)") (class "Default")
      (node (ref "SV11") (pin "14") (pinfunction "7_14") (pintype "passive"))
    )
    (net (code "181") (name "unconnected-(SV11-8-Pad15)") (class "Default")
      (node (ref "SV11") (pin "15") (pinfunction "8_15") (pintype "passive"))
    )
    (net (code "182") (name "unconnected-(SV11-9-Pad16)") (class "Default")
      (node (ref "SV11") (pin "16") (pinfunction "9_16") (pintype "passive"))
    )
    (net (code "183") (name "unconnected-(SV11-10-Pad17)") (class "Default")
      (node (ref "SV11") (pin "17") (pinfunction "10_17") (pintype "passive"))
    )
    (net (code "184") (name "unconnected-(SV11-11-Pad18)") (class "Default")
      (node (ref "SV11") (pin "18") (pinfunction "11_18") (pintype "passive"))
    )
    (net (code "185") (name "unconnected-(SV11-12-Pad19)") (class "Default")
      (node (ref "SV11") (pin "19") (pinfunction "12_19") (pintype "passive"))
    )
    (net (code "186") (name "unconnected-(SV11-13-Pad20)") (class "Default")
      (node (ref "SV11") (pin "20") (pinfunction "13_20") (pintype "passive"))
    )
    (net (code "187") (name "unconnected-(SV11-14-Pad21)") (class "Default")
      (node (ref "SV11") (pin "21") (pinfunction "14_21") (pintype "passive"))
    )
    (net (code "188") (name "unconnected-(SV13-1-Pad2)") (class "Default")
      (node (ref "SV13") (pin "2") (pinfunction "1_2") (pintype "passive"))
    )
    (net (code "189") (name "unconnected-(SV13-2-Pad4)") (class "Default")
      (node (ref "SV13") (pin "4") (pinfunction "2_4") (pintype "passive"))
    )
    (net (code "190") (name "unconnected-(SV13-3-Pad6)") (class "Default")
      (node (ref "SV13") (pin "6") (pinfunction "3_6") (pintype "passive"))
    )
    (net (code "191") (name "unconnected-(SV13-4-Pad8)") (class "Default")
      (node (ref "SV13") (pin "8") (pinfunction "4_8") (pintype "passive"))
    )
    (net (code "192") (name "unconnected-(SV13-5-Pad10)") (class "Default")
      (node (ref "SV13") (pin "10") (pinfunction "5_10") (pintype "passive"))
    )
    (net (code "193") (name "unconnected-(SV13-6-Pad12)") (class "Default")
      (node (ref "SV13") (pin "12") (pinfunction "6_12") (pintype "passive"))
    )
    (net (code "194") (name "unconnected-(SV13-7-Pad14)") (class "Default")
      (node (ref "SV13") (pin "14") (pinfunction "7_14") (pintype "passive"))
    )
    (net (code "195") (name "unconnected-(SV13-8-Pad15)") (class "Default")
      (node (ref "SV13") (pin "15") (pinfunction "8_15") (pintype "passive"))
    )
    (net (code "196") (name "unconnected-(SV13-9-Pad16)") (class "Default")
      (node (ref "SV13") (pin "16") (pinfunction "9_16") (pintype "passive"))
    )
    (net (code "197") (name "unconnected-(SV13-10-Pad17)") (class "Default")
      (node (ref "SV13") (pin "17") (pinfunction "10_17") (pintype "passive"))
    )
    (net (code "198") (name "unconnected-(SV13-11-Pad18)") (class "Default")
      (node (ref "SV13") (pin "18") (pinfunction "11_18") (pintype "passive"))
    )
    (net (code "199") (name "unconnected-(SV13-12-Pad19)") (class "Default")
      (node (ref "SV13") (pin "19") (pinfunction "12_19") (pintype "passive"))
    )
    (net (code "200") (name "unconnected-(SV13-13-Pad20)") (class "Default")
      (node (ref "SV13") (pin "20") (pinfunction "13_20") (pintype "passive"))
    )
    (net (code "201") (name "unconnected-(SV13-14-Pad21)") (class "Default")
      (node (ref "SV13") (pin "21") (pinfunction "14_21") (pintype "passive"))
    )
    (net (code "202") (name "unconnected-(SV14-1-Pad2)") (class "Default")
      (node (ref "SV14") (pin "2") (pinfunction "1_2") (pintype "passive"))
    )
    (net (code "203") (name "unconnected-(SV14-2-Pad4)") (class "Default")
      (node (ref "SV14") (pin "4") (pinfunction "2_4") (pintype "passive"))
    )
    (net (code "204") (name "unconnected-(SV14-3-Pad6)") (class "Default")
      (node (ref "SV14") (pin "6") (pinfunction "3_6") (pintype "passive"))
    )
    (net (code "205") (name "unconnected-(SV14-4-Pad8)") (class "Default")
      (node (ref "SV14") (pin "8") (pinfunction "4_8") (pintype "passive"))
    )
    (net (code "206") (name "unconnected-(SV14-5-Pad10)") (class "Default")
      (node (ref "SV14") (pin "10") (pinfunction "5_10") (pintype "passive"))
    )
    (net (code "207") (name "unconnected-(SV14-6-Pad12)") (class "Default")
      (node (ref "SV14") (pin "12") (pinfunction "6_12") (pintype "passive"))
    )
    (net (code "208") (name "unconnected-(SV14-7-Pad14)") (class "Default")
      (node (ref "SV14") (pin "14") (pinfunction "7_14") (pintype "passive"))
    )
    (net (code "209") (name "unconnected-(SV14-8-Pad15)") (class "Default")
      (node (ref "SV14") (pin "15") (pinfunction "8_15") (pintype "passive"))
    )
    (net (code "210") (name "unconnected-(SV14-9-Pad16)") (class "Default")
      (node (ref "SV14") (pin "16") (pinfunction "9_16") (pintype "passive"))
    )
    (net (code "211") (name "unconnected-(SV14-10-Pad17)") (class "Default")
      (node (ref "SV14") (pin "17") (pinfunction "10_17") (pintype "passive"))
    )
    (net (code "212") (name "unconnected-(SV14-11-Pad18)") (class "Default")
      (node (ref "SV14") (pin "18") (pinfunction "11_18") (pintype "passive"))
    )
    (net (code "213") (name "unconnected-(SV14-12-Pad19)") (class "Default")
      (node (ref "SV14") (pin "19") (pinfunction "12_19") (pintype "passive"))
    )
    (net (code "214") (name "unconnected-(SV14-13-Pad20)") (class "Default")
      (node (ref "SV14") (pin "20") (pinfunction "13_20") (pintype "passive"))
    )
    (net (code "215") (name "unconnected-(SV14-14-Pad21)") (class "Default")
      (node (ref "SV14") (pin "21") (pinfunction "14_21") (pintype "passive"))
    )
  )
)
